# Three_Phase_Inverter.net
KiCad netlist of a schematic drawn in Altium Designer
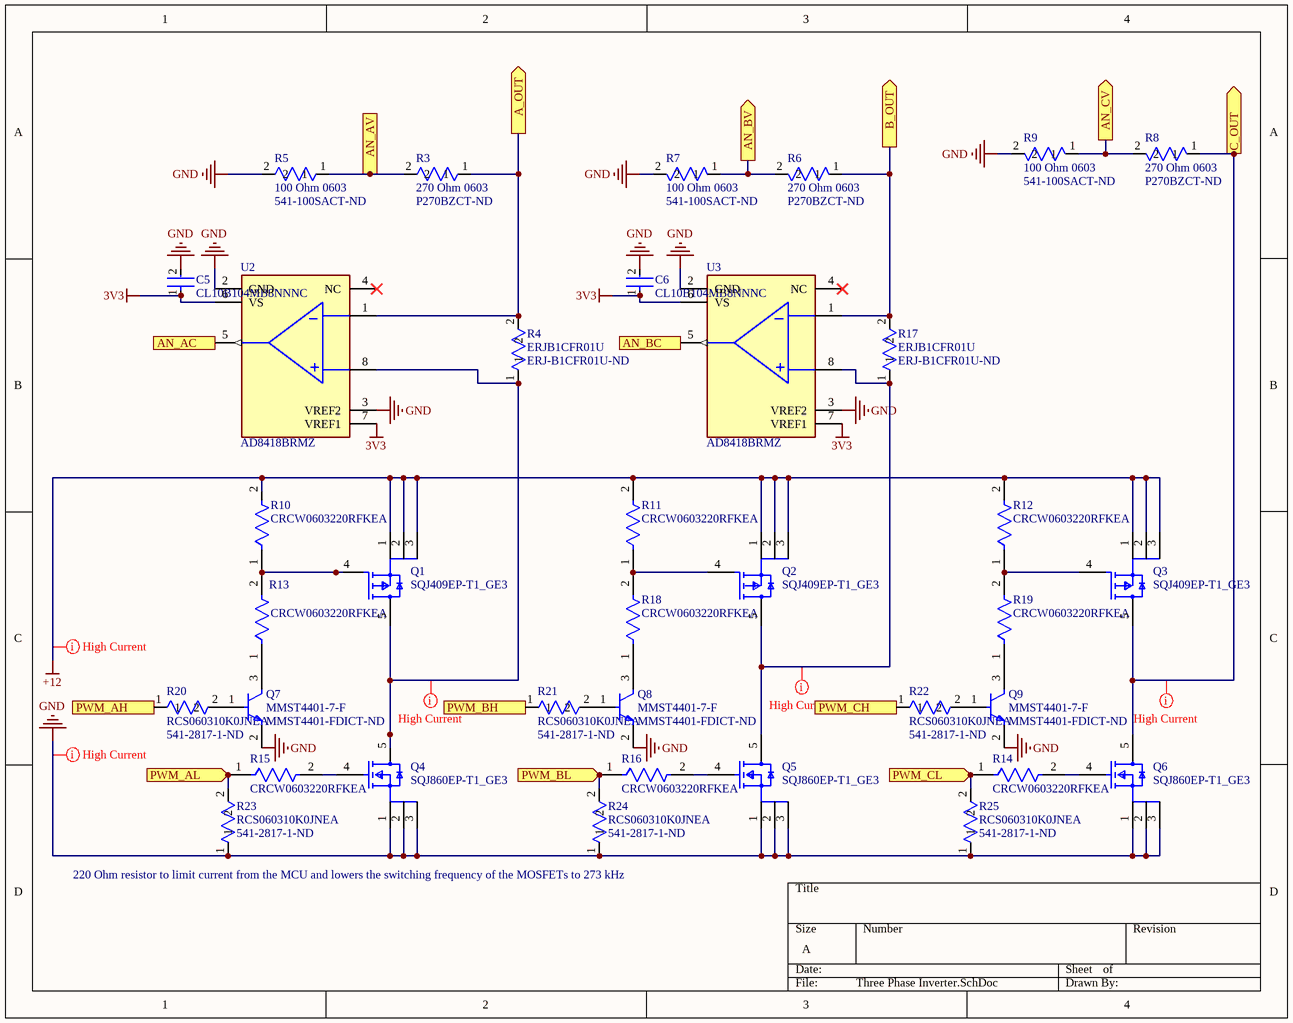
[diagram p0: Three Phase Inverter.SchDoc]

(export (version "E")
  (design (tool "Eeschema 10.0.6"))
  (components
    (comp (ref "C5")
      (value "CL10B104MB8NNNC")
      (footprint "FP-CL10-IPC_C")
      (description "Cap Ceramic 100nF 50V X7R ±20% Pad SMD 0603 +125°C T/R")
      (fields (field (name "TOLERANCE") "20%"))
      (libsource (lib "Altium Content Vault") (part "b4654b650e69147ec39a6b967a45e02"))
    )
    (comp (ref "C6")
      (value "CL10B104MB8NNNC")
      (footprint "FP-CL10-IPC_C")
      (description "Cap Ceramic 100nF 50V X7R ±20% Pad SMD 0603 +125°C T/R")
      (fields (field (name "TOLERANCE") "20%"))
      (libsource (lib "Altium Content Vault") (part "b4654b650e69147ec39a6b967a45e02"))
    )
    (comp (ref "Q1")
      (value "SQJ409EP-T1_GE3")
      (footprint "SQJ409EP-T1_GE3")
      (libsource (lib "Schematic Library") (part "SQJ409EP-T1_GE3"))
    )
    (comp (ref "Q2")
      (value "SQJ409EP-T1_GE3")
      (footprint "SQJ409EP-T1_GE3")
      (libsource (lib "Schematic Library") (part "SQJ409EP-T1_GE3"))
    )
    (comp (ref "Q3")
      (value "SQJ409EP-T1_GE3")
      (footprint "SQJ409EP-T1_GE3")
      (libsource (lib "Schematic Library") (part "SQJ409EP-T1_GE3"))
    )
    (comp (ref "Q4")
      (value "SQJ860EP-T1_GE3")
      (footprint "SQJ860EP")
      (description "RESET GENERATOR SOT23")
      (fields (field (name "MANUFACTURER") "Vishay"))
      (libsource (lib "Schematic Library") (part "SQJ860EP-T1_GE3"))
    )
    (comp (ref "Q5")
      (value "SQJ860EP-T1_GE3")
      (footprint "SQJ860EP")
      (description "RESET GENERATOR SOT23")
      (fields (field (name "MANUFACTURER") "Vishay"))
      (libsource (lib "Schematic Library") (part "SQJ860EP-T1_GE3"))
    )
    (comp (ref "Q6")
      (value "SQJ860EP-T1_GE3")
      (footprint "SQJ860EP")
      (description "RESET GENERATOR SOT23")
      (fields (field (name "MANUFACTURER") "Vishay"))
      (libsource (lib "Schematic Library") (part "SQJ860EP-T1_GE3"))
    )
    (comp (ref "Q7")
      (value "MMST4401-7-F")
      (footprint "MMST4401-7-F")
      (description "TRANS NPN 40V 0.6A SC70-3")
      (fields
        (field (name "MANUFACTURER") "Diodes")
        (field (name "SUPPLIER PART NUMBER 1") "MMST4401-FDICT-ND")
      )
      (libsource (lib "Schematic Library") (part "MMST4401-7-F"))
    )
    (comp (ref "Q8")
      (value "MMST4401-7-F")
      (footprint "MMST4401-7-F")
      (description "TRANS NPN 40V 0.6A SC70-3")
      (fields
        (field (name "MANUFACTURER") "Diodes")
        (field (name "SUPPLIER PART NUMBER 1") "MMST4401-FDICT-ND")
      )
      (libsource (lib "Schematic Library") (part "MMST4401-7-F"))
    )
    (comp (ref "Q9")
      (value "MMST4401-7-F")
      (footprint "MMST4401-7-F")
      (description "TRANS NPN 40V 0.6A SC70-3")
      (fields
        (field (name "MANUFACTURER") "Diodes")
        (field (name "SUPPLIER PART NUMBER 1") "MMST4401-FDICT-ND")
      )
      (libsource (lib "Schematic Library") (part "MMST4401-7-F"))
    )
    (comp (ref "R3")
      (value "270 Ohm 0603")
      (footprint "ERJ-PA3J271V")
      (description "Res Thick Film 0603 270 Ohm 5% 0.25W(1/4W) ±200ppm/C Pad SMD Automotive T/R")
      (fields
        (field (name "MANUFACTURER") "Panasonic")
        (field (name "MANUFACTURER PART NUMBER") "ERJ-PA3J271V")
        (field (name "SUPPLIER PART NUMBER 1") "P270BZCT-ND")
      )
      (libsource (lib "Schematic Library") (part "ERJ-PA3J271V"))
    )
    (comp (ref "R4")
      (value "ERJB1CFR01U")
      (footprint "ERJ-B1CFR01U")
      (description "Res Thick Film 1020 0.01 Ohm 1% 2W ±350ppm/°C Molded SMD Embossed Carrier T/R")
      (fields
        (field (name "MANUFACTURER") "Panasonic")
        (field (name "TOLERANCE") "1%")
        (field (name "SUPPLIER PART NUMBER 1") "ERJ-B1CFR01U-ND")
      )
      (libsource (lib "Schematic Library") (part "ERJB1CFR01U"))
    )
    (comp (ref "R5")
      (value "100 Ohm 0603")
      (footprint "CRCW0603100RJNEAHP")
      (description "Res Thick Film 0603 100 Ohm 5% 1/4W 200ppm/C Molded SMD SMD Paper T/R")
      (fields
        (field (name "MANUFACTURER") "Vishay Dale")
        (field (name "MANUFACTURER PART NUMBER") "CRCW0603100RJNEAHP")
        (field (name "SUPPLIER PART NUMBER 1") "541-100SACT-ND")
      )
      (libsource (lib "Schematic Library") (part "CRCW0603100RJNEAHP"))
    )
    (comp (ref "R6")
      (value "270 Ohm 0603")
      (footprint "ERJ-PA3J271V")
      (description "Res Thick Film 0603 270 Ohm 5% 0.25W(1/4W) ±200ppm/C Pad SMD Automotive T/R")
      (fields
        (field (name "MANUFACTURER") "Panasonic")
        (field (name "MANUFACTURER PART NUMBER") "ERJ-PA3J271V")
        (field (name "SUPPLIER PART NUMBER 1") "P270BZCT-ND")
      )
      (libsource (lib "Schematic Library") (part "ERJ-PA3J271V"))
    )
    (comp (ref "R7")
      (value "100 Ohm 0603")
      (footprint "CRCW0603100RJNEAHP")
      (description "Res Thick Film 0603 100 Ohm 5% 1/4W 200ppm/C Molded SMD SMD Paper T/R")
      (fields
        (field (name "MANUFACTURER") "Vishay Dale")
        (field (name "MANUFACTURER PART NUMBER") "CRCW0603100RJNEAHP")
        (field (name "SUPPLIER PART NUMBER 1") "541-100SACT-ND")
      )
      (libsource (lib "Schematic Library") (part "CRCW0603100RJNEAHP"))
    )
    (comp (ref "R8")
      (value "270 Ohm 0603")
      (footprint "ERJ-PA3J271V")
      (description "Res Thick Film 0603 270 Ohm 5% 0.25W(1/4W) ±200ppm/C Pad SMD Automotive T/R")
      (fields
        (field (name "MANUFACTURER") "Panasonic")
        (field (name "MANUFACTURER PART NUMBER") "ERJ-PA3J271V")
        (field (name "SUPPLIER PART NUMBER 1") "P270BZCT-ND")
      )
      (libsource (lib "Schematic Library") (part "ERJ-PA3J271V"))
    )
    (comp (ref "R9")
      (value "100 Ohm 0603")
      (footprint "CRCW0603100RJNEAHP")
      (description "Res Thick Film 0603 100 Ohm 5% 1/4W 200ppm/C Molded SMD SMD Paper T/R")
      (fields
        (field (name "MANUFACTURER") "Vishay Dale")
        (field (name "MANUFACTURER PART NUMBER") "CRCW0603100RJNEAHP")
        (field (name "SUPPLIER PART NUMBER 1") "541-100SACT-ND")
      )
      (libsource (lib "Schematic Library") (part "CRCW0603100RJNEAHP"))
    )
    (comp (ref "R10")
      (value "CRCW0603220RFKEA")
      (footprint "FP-CRCW0603-e3-MFG")
      (description "RES Thick Film, 220Ω, 1%, 0.1W, 100ppm/°C, 0603")
      (fields (field (name "TOLERANCE") "1%"))
      (libsource (lib "Altium Content Vault") (part "1029c3af85768c4190bb7ad29bc67b5"))
    )
    (comp (ref "R11")
      (value "CRCW0603220RFKEA")
      (footprint "FP-CRCW0603-e3-MFG")
      (description "RES Thick Film, 220Ω, 1%, 0.1W, 100ppm/°C, 0603")
      (fields (field (name "TOLERANCE") "1%"))
      (libsource (lib "Altium Content Vault") (part "1029c3af85768c4190bb7ad29bc67b5"))
    )
    (comp (ref "R12")
      (value "CRCW0603220RFKEA")
      (footprint "FP-CRCW0603-e3-MFG")
      (description "RES Thick Film, 220Ω, 1%, 0.1W, 100ppm/°C, 0603")
      (fields (field (name "TOLERANCE") "1%"))
      (libsource (lib "Altium Content Vault") (part "1029c3af85768c4190bb7ad29bc67b5"))
    )
    (comp (ref "R13")
      (value "CRCW0603220RFKEA")
      (footprint "FP-CRCW0603-e3-MFG")
      (description "RES Thick Film, 220Ω, 1%, 0.1W, 100ppm/°C, 0603")
      (fields (field (name "TOLERANCE") "1%"))
      (libsource (lib "Altium Content Vault") (part "1029c3af85768c4190bb7ad29bc67b5"))
    )
    (comp (ref "R14")
      (value "CRCW0603220RFKEA")
      (footprint "FP-CRCW0603-e3-MFG")
      (description "RES Thick Film, 220Ω, 1%, 0.1W, 100ppm/°C, 0603")
      (fields (field (name "TOLERANCE") "1%"))
      (libsource (lib "Altium Content Vault") (part "1029c3af85768c4190bb7ad29bc67b5"))
    )
    (comp (ref "R15")
      (value "CRCW0603220RFKEA")
      (footprint "FP-CRCW0603-e3-MFG")
      (description "RES Thick Film, 220Ω, 1%, 0.1W, 100ppm/°C, 0603")
      (fields (field (name "TOLERANCE") "1%"))
      (libsource (lib "Altium Content Vault") (part "1029c3af85768c4190bb7ad29bc67b5"))
    )
    (comp (ref "R16")
      (value "CRCW0603220RFKEA")
      (footprint "FP-CRCW0603-e3-MFG")
      (description "RES Thick Film, 220Ω, 1%, 0.1W, 100ppm/°C, 0603")
      (fields (field (name "TOLERANCE") "1%"))
      (libsource (lib "Altium Content Vault") (part "1029c3af85768c4190bb7ad29bc67b5"))
    )
    (comp (ref "R17")
      (value "ERJB1CFR01U")
      (footprint "ERJ-B1CFR01U")
      (description "Res Thick Film 1020 0.01 Ohm 1% 2W ±350ppm/°C Molded SMD Embossed Carrier T/R")
      (fields
        (field (name "MANUFACTURER") "Panasonic")
        (field (name "TOLERANCE") "1%")
        (field (name "SUPPLIER PART NUMBER 1") "ERJ-B1CFR01U-ND")
      )
      (libsource (lib "Schematic Library") (part "ERJB1CFR01U"))
    )
    (comp (ref "R18")
      (value "CRCW0603220RFKEA")
      (footprint "FP-CRCW0603-e3-MFG")
      (description "RES Thick Film, 220Ω, 1%, 0.1W, 100ppm/°C, 0603")
      (fields (field (name "TOLERANCE") "1%"))
      (libsource (lib "Altium Content Vault") (part "1029c3af85768c4190bb7ad29bc67b5"))
    )
    (comp (ref "R19")
      (value "CRCW0603220RFKEA")
      (footprint "FP-CRCW0603-e3-MFG")
      (description "RES Thick Film, 220Ω, 1%, 0.1W, 100ppm/°C, 0603")
      (fields (field (name "TOLERANCE") "1%"))
      (libsource (lib "Altium Content Vault") (part "1029c3af85768c4190bb7ad29bc67b5"))
    )
    (comp (ref "R20")
      (value "RCS060310K0JNEA")
      (footprint "RCS060310K0JNEA")
      (description "RES SMD 10K OHM 5% 1/4W 0603")
      (fields
        (field (name "MANUFACTURER") "Vishay Dale")
        (field (name "TOLERANCE") "5%")
        (field (name "SUPPLIER PART NUMBER 1") "541-2817-1-ND")
      )
      (libsource (lib "Schematic Library") (part "RCS060310K0JNEA"))
    )
    (comp (ref "R21")
      (value "RCS060310K0JNEA")
      (footprint "RCS060310K0JNEA")
      (description "RES SMD 10K OHM 5% 1/4W 0603")
      (fields
        (field (name "MANUFACTURER") "Vishay Dale")
        (field (name "TOLERANCE") "5%")
        (field (name "SUPPLIER PART NUMBER 1") "541-2817-1-ND")
      )
      (libsource (lib "Schematic Library") (part "RCS060310K0JNEA"))
    )
    (comp (ref "R22")
      (value "RCS060310K0JNEA")
      (footprint "RCS060310K0JNEA")
      (description "RES SMD 10K OHM 5% 1/4W 0603")
      (fields
        (field (name "MANUFACTURER") "Vishay Dale")
        (field (name "TOLERANCE") "5%")
        (field (name "SUPPLIER PART NUMBER 1") "541-2817-1-ND")
      )
      (libsource (lib "Schematic Library") (part "RCS060310K0JNEA"))
    )
    (comp (ref "R23")
      (value "RCS060310K0JNEA")
      (footprint "RCS060310K0JNEA")
      (description "RES SMD 10K OHM 5% 1/4W 0603")
      (fields
        (field (name "MANUFACTURER") "Vishay Dale")
        (field (name "TOLERANCE") "5%")
        (field (name "SUPPLIER PART NUMBER 1") "541-2817-1-ND")
      )
      (libsource (lib "Schematic Library") (part "RCS060310K0JNEA"))
    )
    (comp (ref "R24")
      (value "RCS060310K0JNEA")
      (footprint "RCS060310K0JNEA")
      (description "RES SMD 10K OHM 5% 1/4W 0603")
      (fields
        (field (name "MANUFACTURER") "Vishay Dale")
        (field (name "TOLERANCE") "5%")
        (field (name "SUPPLIER PART NUMBER 1") "541-2817-1-ND")
      )
      (libsource (lib "Schematic Library") (part "RCS060310K0JNEA"))
    )
    (comp (ref "R25")
      (value "RCS060310K0JNEA")
      (footprint "RCS060310K0JNEA")
      (description "RES SMD 10K OHM 5% 1/4W 0603")
      (fields
        (field (name "MANUFACTURER") "Vishay Dale")
        (field (name "TOLERANCE") "5%")
        (field (name "SUPPLIER PART NUMBER 1") "541-2817-1-ND")
      )
      (libsource (lib "Schematic Library") (part "RCS060310K0JNEA"))
    )
    (comp (ref "U2")
      (value "AD8418BRMZ")
      (footprint "FP-RM-8-IPC_C")
      (description "IC CURR SENSE 1 CIRCUIT 8MSOP")
      (fields
        (field (name "OCTOPART") "https://octopart.com/ad8418brmz-analog+devices-21054230")
        (field (name "MANUFACTURER") "Analog Devices")
      )
      (libsource (lib "Altium Content Vault") (part "03744de002b8bba09019ca20017b8fc"))
    )
    (comp (ref "U3")
      (value "AD8418BRMZ")
      (footprint "FP-RM-8-IPC_C")
      (description "IC CURR SENSE 1 CIRCUIT 8MSOP")
      (fields
        (field (name "OCTOPART") "https://octopart.com/ad8418brmz-analog+devices-21054230")
        (field (name "MANUFACTURER") "Analog Devices")
      )
      (libsource (lib "Altium Content Vault") (part "03744de002b8bba09019ca20017b8fc"))
    )
  )
  (nets
    (net (code "1") (name "+12") (class "Default")
      (node (ref "Q1") (pin "1") (pinfunction "S_1") (pintype "passive"))
      (node (ref "Q1") (pin "2") (pinfunction "S_2") (pintype "passive"))
      (node (ref "Q1") (pin "3") (pinfunction "S_3") (pintype "passive"))
      (node (ref "Q2") (pin "1") (pinfunction "S_1") (pintype "passive"))
      (node (ref "Q2") (pin "2") (pinfunction "S_2") (pintype "passive"))
      (node (ref "Q2") (pin "3") (pinfunction "S_3") (pintype "passive"))
      (node (ref "Q3") (pin "1") (pinfunction "S_1") (pintype "passive"))
      (node (ref "Q3") (pin "2") (pinfunction "S_2") (pintype "passive"))
      (node (ref "Q3") (pin "3") (pinfunction "S_3") (pintype "passive"))
      (node (ref "R10") (pin "2") (pinfunction "2_2") (pintype "passive"))
      (node (ref "R11") (pin "2") (pinfunction "2_2") (pintype "passive"))
      (node (ref "R12") (pin "2") (pinfunction "2_2") (pintype "passive"))
    )
    (net (code "2") (name "/AN_AC") (class "Default")
      (node (ref "U2") (pin "5") (pinfunction "OUT_5") (pintype "output"))
    )
    (net (code "3") (name "/AN_AV") (class "Default")
      (node (ref "R3") (pin "2") (pinfunction "2_2") (pintype "passive"))
      (node (ref "R5") (pin "1") (pinfunction "1_1") (pintype "passive"))
    )
    (net (code "4") (name "/AN_BC") (class "Default")
      (node (ref "U3") (pin "5") (pinfunction "OUT_5") (pintype "output"))
    )
    (net (code "5") (name "/AN_BV") (class "Default")
      (node (ref "R6") (pin "2") (pinfunction "2_2") (pintype "passive"))
      (node (ref "R7") (pin "1") (pinfunction "1_1") (pintype "passive"))
    )
    (net (code "6") (name "/AN_CV") (class "Default")
      (node (ref "R8") (pin "2") (pinfunction "2_2") (pintype "passive"))
      (node (ref "R9") (pin "1") (pinfunction "1_1") (pintype "passive"))
    )
    (net (code "7") (name "/A_OUT") (class "Default")
      (node (ref "R3") (pin "1") (pinfunction "1_1") (pintype "passive"))
      (node (ref "R4") (pin "2") (pinfunction "2_2") (pintype "passive"))
      (node (ref "U2") (pin "1") (pinfunction "-IN_1") (pintype "tri_state"))
    )
    (net (code "8") (name "/B_OUT") (class "Default")
      (node (ref "R17") (pin "2") (pinfunction "2_2") (pintype "passive"))
      (node (ref "R6") (pin "1") (pinfunction "1_1") (pintype "passive"))
      (node (ref "U3") (pin "1") (pinfunction "-IN_1") (pintype "tri_state"))
    )
    (net (code "9") (name "/C_OUT") (class "Default")
      (node (ref "Q3") (pin "5") (pinfunction "D_5") (pintype "passive"))
      (node (ref "Q6") (pin "5") (pinfunction "D_5") (pintype "passive"))
      (node (ref "R8") (pin "1") (pinfunction "1_1") (pintype "passive"))
    )
    (net (code "10") (name "/PWM_AH") (class "Default")
      (node (ref "R20") (pin "1") (pinfunction "1_1") (pintype "passive"))
    )
    (net (code "11") (name "/PWM_AL") (class "Default")
      (node (ref "R15") (pin "1") (pinfunction "1_1") (pintype "passive"))
      (node (ref "R23") (pin "2") (pinfunction "2_2") (pintype "passive"))
    )
    (net (code "12") (name "/PWM_BH") (class "Default")
      (node (ref "R21") (pin "1") (pinfunction "1_1") (pintype "passive"))
    )
    (net (code "13") (name "/PWM_BL") (class "Default")
      (node (ref "R16") (pin "1") (pinfunction "1_1") (pintype "passive"))
      (node (ref "R24") (pin "2") (pinfunction "2_2") (pintype "passive"))
    )
    (net (code "14") (name "/PWM_CH") (class "Default")
      (node (ref "R22") (pin "1") (pinfunction "1_1") (pintype "passive"))
    )
    (net (code "15") (name "/PWM_CL") (class "Default")
      (node (ref "R14") (pin "1") (pinfunction "1_1") (pintype "passive"))
      (node (ref "R25") (pin "2") (pinfunction "2_2") (pintype "passive"))
    )
    (net (code "16") (name "3V3") (class "Default")
      (node (ref "C5") (pin "1") (pinfunction "1_1") (pintype "passive"))
      (node (ref "C6") (pin "1") (pinfunction "1_1") (pintype "passive"))
      (node (ref "U2") (pin "6") (pinfunction "VS_6") (pintype "power_in"))
      (node (ref "U2") (pin "7") (pinfunction "VREF1_7") (pintype "power_in"))
      (node (ref "U3") (pin "6") (pinfunction "VS_6") (pintype "power_in"))
      (node (ref "U3") (pin "7") (pinfunction "VREF1_7") (pintype "power_in"))
    )
    (net (code "17") (name "GND") (class "Default")
      (node (ref "C5") (pin "2") (pinfunction "2_2") (pintype "passive"))
      (node (ref "C6") (pin "2") (pinfunction "2_2") (pintype "passive"))
      (node (ref "Q4") (pin "1") (pinfunction "S_1") (pintype "passive"))
      (node (ref "Q4") (pin "2") (pinfunction "S_2") (pintype "passive"))
      (node (ref "Q4") (pin "3") (pinfunction "S_3") (pintype "passive"))
      (node (ref "Q5") (pin "1") (pinfunction "S_1") (pintype "passive"))
      (node (ref "Q5") (pin "2") (pinfunction "S_2") (pintype "passive"))
      (node (ref "Q5") (pin "3") (pinfunction "S_3") (pintype "passive"))
      (node (ref "Q6") (pin "1") (pinfunction "S_1") (pintype "passive"))
      (node (ref "Q6") (pin "2") (pinfunction "S_2") (pintype "passive"))
      (node (ref "Q6") (pin "3") (pinfunction "S_3") (pintype "passive"))
      (node (ref "Q7") (pin "2") (pinfunction "E_2") (pintype "passive"))
      (node (ref "Q8") (pin "2") (pinfunction "E_2") (pintype "passive"))
      (node (ref "Q9") (pin "2") (pinfunction "E_2") (pintype "passive"))
      (node (ref "R23") (pin "1") (pinfunction "1_1") (pintype "passive"))
      (node (ref "R24") (pin "1") (pinfunction "1_1") (pintype "passive"))
      (node (ref "R25") (pin "1") (pinfunction "1_1") (pintype "passive"))
      (node (ref "R5") (pin "2") (pinfunction "2_2") (pintype "passive"))
      (node (ref "R7") (pin "2") (pinfunction "2_2") (pintype "passive"))
      (node (ref "R9") (pin "2") (pinfunction "2_2") (pintype "passive"))
      (node (ref "U2") (pin "2") (pinfunction "GND_2") (pintype "power_in"))
      (node (ref "U2") (pin "3") (pinfunction "VREF2_3") (pintype "power_in"))
      (node (ref "U3") (pin "2") (pinfunction "GND_2") (pintype "power_in"))
      (node (ref "U3") (pin "3") (pinfunction "VREF2_3") (pintype "power_in"))
    )
    (net (code "18") (name "Net-(Q1-D)") (class "Default")
      (node (ref "Q1") (pin "5") (pinfunction "D_5") (pintype "passive"))
      (node (ref "Q4") (pin "5") (pinfunction "D_5") (pintype "passive"))
      (node (ref "R4") (pin "1") (pinfunction "1_1") (pintype "passive"))
      (node (ref "U2") (pin "8") (pinfunction "+IN_8") (pintype "tri_state"))
    )
    (net (code "19") (name "Net-(Q1-G)") (class "Default")
      (node (ref "Q1") (pin "4") (pinfunction "G_4") (pintype "passive"))
      (node (ref "R10") (pin "1") (pinfunction "1_1") (pintype "passive"))
      (node (ref "R13") (pin "2") (pinfunction "2_2") (pintype "passive"))
    )
    (net (code "20") (name "Net-(Q2-D)") (class "Default")
      (node (ref "Q2") (pin "5") (pinfunction "D_5") (pintype "passive"))
      (node (ref "Q5") (pin "5") (pinfunction "D_5") (pintype "passive"))
      (node (ref "R17") (pin "1") (pinfunction "1_1") (pintype "passive"))
      (node (ref "U3") (pin "8") (pinfunction "+IN_8") (pintype "tri_state"))
    )
    (net (code "21") (name "Net-(Q2-G)") (class "Default")
      (node (ref "Q2") (pin "4") (pinfunction "G_4") (pintype "passive"))
      (node (ref "R11") (pin "1") (pinfunction "1_1") (pintype "passive"))
      (node (ref "R18") (pin "2") (pinfunction "2_2") (pintype "passive"))
    )
    (net (code "22") (name "Net-(Q3-G)") (class "Default")
      (node (ref "Q3") (pin "4") (pinfunction "G_4") (pintype "passive"))
      (node (ref "R12") (pin "1") (pinfunction "1_1") (pintype "passive"))
      (node (ref "R19") (pin "2") (pinfunction "2_2") (pintype "passive"))
    )
    (net (code "23") (name "Net-(Q4-G)") (class "Default")
      (node (ref "Q4") (pin "4") (pinfunction "G_4") (pintype "passive"))
      (node (ref "R15") (pin "2") (pinfunction "2_2") (pintype "passive"))
    )
    (net (code "24") (name "Net-(Q5-G)") (class "Default")
      (node (ref "Q5") (pin "4") (pinfunction "G_4") (pintype "passive"))
      (node (ref "R16") (pin "2") (pinfunction "2_2") (pintype "passive"))
    )
    (net (code "25") (name "Net-(Q6-G)") (class "Default")
      (node (ref "Q6") (pin "4") (pinfunction "G_4") (pintype "passive"))
      (node (ref "R14") (pin "2") (pinfunction "2_2") (pintype "passive"))
    )
    (net (code "26") (name "Net-(Q7-B)") (class "Default")
      (node (ref "Q7") (pin "1") (pinfunction "B_1") (pintype "passive"))
      (node (ref "R20") (pin "2") (pinfunction "2_2") (pintype "passive"))
    )
    (net (code "27") (name "Net-(Q7-C)") (class "Default")
      (node (ref "Q7") (pin "3") (pinfunction "C_3") (pintype "passive"))
      (node (ref "R13") (pin "1") (pinfunction "1_1") (pintype "passive"))
    )
    (net (code "28") (name "Net-(Q8-B)") (class "Default")
      (node (ref "Q8") (pin "1") (pinfunction "B_1") (pintype "passive"))
      (node (ref "R21") (pin "2") (pinfunction "2_2") (pintype "passive"))
    )
    (net (code "29") (name "Net-(Q8-C)") (class "Default")
      (node (ref "Q8") (pin "3") (pinfunction "C_3") (pintype "passive"))
      (node (ref "R18") (pin "1") (pinfunction "1_1") (pintype "passive"))
    )
    (net (code "30") (name "Net-(Q9-B)") (class "Default")
      (node (ref "Q9") (pin "1") (pinfunction "B_1") (pintype "passive"))
      (node (ref "R22") (pin "2") (pinfunction "2_2") (pintype "passive"))
    )
    (net (code "31") (name "Net-(Q9-C)") (class "Default")
      (node (ref "Q9") (pin "3") (pinfunction "C_3") (pintype "passive"))
      (node (ref "R19") (pin "1") (pinfunction "1_1") (pintype "passive"))
    )
    (net (code "32") (name "unconnected-(U2-NC-Pad4)") (class "Default")
      (node (ref "U2") (pin "4") (pinfunction "NC_4") (pintype "passive+no_connect"))
    )
    (net (code "33") (name "unconnected-(U3-NC-Pad4)") (class "Default")
      (node (ref "U3") (pin "4") (pinfunction "NC_4") (pintype "passive+no_connect"))
    )
  )
)
